# CCM_0008.net
KiCad netlist of a schematic drawn in EAGLE
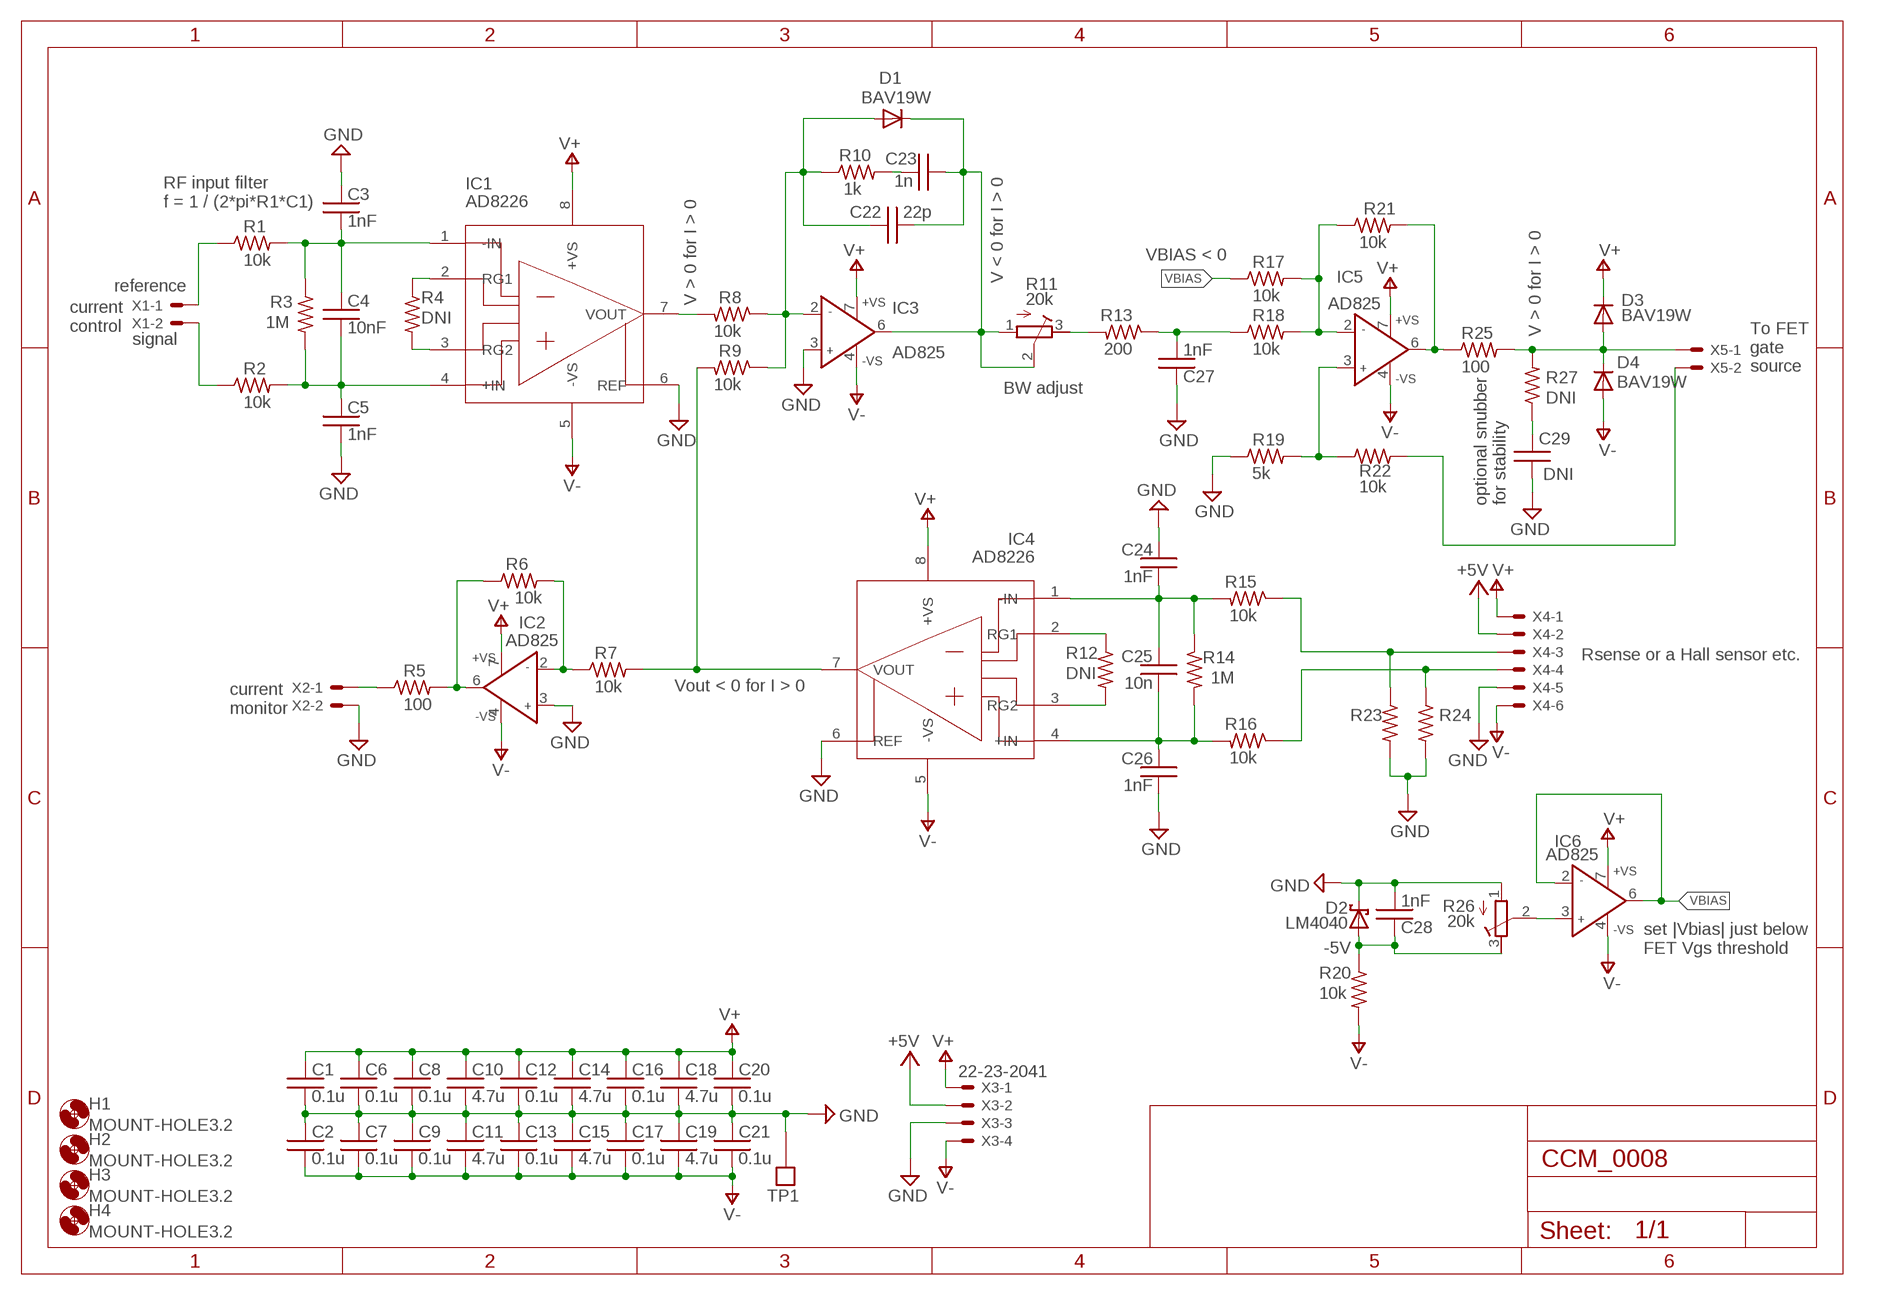
[diagram p0: schematic, sheet 1]

(export (version "E")
  (design (tool "Eeschema 10.0.6"))
  (components
    (comp (ref "C1")
      (value "0.1u")
      (footprint "eagle-import:0603")
      (libsource (lib "eagle-import") (part "C0603"))
    )
    (comp (ref "C2")
      (value "0.1u")
      (footprint "eagle-import:0603")
      (libsource (lib "eagle-import") (part "C0603"))
    )
    (comp (ref "C3")
      (value "1nF")
      (footprint "eagle-import:0603")
      (libsource (lib "eagle-import") (part "C0603"))
    )
    (comp (ref "C4")
      (value "10nF")
      (footprint "eagle-import:0603")
      (libsource (lib "eagle-import") (part "C0603"))
    )
    (comp (ref "C5")
      (value "1nF")
      (footprint "eagle-import:0603")
      (libsource (lib "eagle-import") (part "C0603"))
    )
    (comp (ref "C6")
      (value "0.1u")
      (footprint "eagle-import:0603")
      (libsource (lib "eagle-import") (part "C0603"))
    )
    (comp (ref "C7")
      (value "0.1u")
      (footprint "eagle-import:0603")
      (libsource (lib "eagle-import") (part "C0603"))
    )
    (comp (ref "C8")
      (value "0.1u")
      (footprint "eagle-import:0603")
      (libsource (lib "eagle-import") (part "C0603"))
    )
    (comp (ref "C9")
      (value "0.1u")
      (footprint "eagle-import:0603")
      (libsource (lib "eagle-import") (part "C0603"))
    )
    (comp (ref "C10")
      (value "4.7u")
      (footprint "eagle-import:0603")
      (libsource (lib "eagle-import") (part "C0603"))
    )
    (comp (ref "C11")
      (value "4.7u")
      (footprint "eagle-import:0603")
      (libsource (lib "eagle-import") (part "C0603"))
    )
    (comp (ref "C12")
      (value "0.1u")
      (footprint "eagle-import:0603")
      (libsource (lib "eagle-import") (part "C0603"))
    )
    (comp (ref "C13")
      (value "0.1u")
      (footprint "eagle-import:0603")
      (libsource (lib "eagle-import") (part "C0603"))
    )
    (comp (ref "C14")
      (value "4.7u")
      (footprint "eagle-import:0603")
      (libsource (lib "eagle-import") (part "C0603"))
    )
    (comp (ref "C15")
      (value "4.7u")
      (footprint "eagle-import:0603")
      (libsource (lib "eagle-import") (part "C0603"))
    )
    (comp (ref "C16")
      (value "0.1u")
      (footprint "eagle-import:0603")
      (libsource (lib "eagle-import") (part "C0603"))
    )
    (comp (ref "C17")
      (value "0.1u")
      (footprint "eagle-import:0603")
      (libsource (lib "eagle-import") (part "C0603"))
    )
    (comp (ref "C18")
      (value "4.7u")
      (footprint "eagle-import:0603")
      (libsource (lib "eagle-import") (part "C0603"))
    )
    (comp (ref "C19")
      (value "4.7u")
      (footprint "eagle-import:0603")
      (libsource (lib "eagle-import") (part "C0603"))
    )
    (comp (ref "C20")
      (value "0.1u")
      (footprint "eagle-import:0603")
      (libsource (lib "eagle-import") (part "C0603"))
    )
    (comp (ref "C21")
      (value "0.1u")
      (footprint "eagle-import:0603")
      (libsource (lib "eagle-import") (part "C0603"))
    )
    (comp (ref "C22")
      (value "22p")
      (footprint "eagle-import:0603")
      (libsource (lib "eagle-import") (part "C0603"))
    )
    (comp (ref "C23")
      (value "1n")
      (footprint "eagle-import:0603")
      (libsource (lib "eagle-import") (part "C0603"))
    )
    (comp (ref "C24")
      (value "1nF")
      (footprint "eagle-import:0603")
      (libsource (lib "eagle-import") (part "C0603"))
    )
    (comp (ref "C25")
      (value "10n")
      (footprint "eagle-import:0603")
      (libsource (lib "eagle-import") (part "C0603"))
    )
    (comp (ref "C26")
      (value "1nF")
      (footprint "eagle-import:0603")
      (libsource (lib "eagle-import") (part "C0603"))
    )
    (comp (ref "C27")
      (value "1nF")
      (footprint "eagle-import:0603")
      (libsource (lib "eagle-import") (part "C0603"))
    )
    (comp (ref "C28")
      (value "1nF")
      (footprint "eagle-import:0603")
      (libsource (lib "eagle-import") (part "C0603"))
    )
    (comp (ref "C29")
      (value "DNI")
      (footprint "eagle-import:0603")
      (libsource (lib "eagle-import") (part "C0603"))
    )
    (comp (ref "D1")
      (value "BAV19W")
      (footprint "eagle-import:SOD123")
      (libsource (lib "eagle-import") (part "DIODE-SOD123"))
    )
    (comp (ref "D2")
      (value "LM4040")
      (footprint "eagle-import:SOT23")
      (libsource (lib "eagle-import") (part "LM4040"))
    )
    (comp (ref "D3")
      (value "BAV19W")
      (footprint "eagle-import:SOD123")
      (libsource (lib "eagle-import") (part "DIODE-SOD123"))
    )
    (comp (ref "D4")
      (value "BAV19W")
      (footprint "eagle-import:SOD123")
      (libsource (lib "eagle-import") (part "DIODE-SOD123"))
    )
    (comp (ref "H1")
      (value "MOUNT-HOLE3.2")
      (footprint "eagle-import:3,2")
      (libsource (lib "eagle-import") (part "MOUNT-HOLE3.2"))
    )
    (comp (ref "H2")
      (value "MOUNT-HOLE3.2")
      (footprint "eagle-import:3,2")
      (libsource (lib "eagle-import") (part "MOUNT-HOLE3.2"))
    )
    (comp (ref "H3")
      (value "MOUNT-HOLE3.2")
      (footprint "eagle-import:3,2")
      (libsource (lib "eagle-import") (part "MOUNT-HOLE3.2"))
    )
    (comp (ref "H4")
      (value "MOUNT-HOLE3.2")
      (footprint "eagle-import:3,2")
      (libsource (lib "eagle-import") (part "MOUNT-HOLE3.2"))
    )
    (comp (ref "IC1")
      (value "AD8226")
      (footprint "eagle-import:SO08")
      (libsource (lib "eagle-import") (part "AD8226"))
    )
    (comp (ref "IC2")
      (value "AD825")
      (footprint "eagle-import:SO8")
      (fields (field (name "MF") "ALTERA CORPORATION") (field (name "MPN") "AD825ARZ"))
      (libsource (lib "eagle-import") (part "AD825_BR"))
    )
    (comp (ref "IC3")
      (value "AD825")
      (footprint "eagle-import:SO8")
      (fields (field (name "MF") "ALTERA CORPORATION") (field (name "MPN") "AD825ARZ"))
      (libsource (lib "eagle-import") (part "AD825_BR"))
    )
    (comp (ref "IC4")
      (value "AD8226")
      (footprint "eagle-import:SO08")
      (libsource (lib "eagle-import") (part "AD8226"))
    )
    (comp (ref "IC5")
      (value "AD825")
      (footprint "eagle-import:SO8")
      (fields (field (name "MF") "ALTERA CORPORATION") (field (name "MPN") "AD825ARZ"))
      (libsource (lib "eagle-import") (part "AD825_BR"))
    )
    (comp (ref "IC6")
      (value "AD825")
      (footprint "eagle-import:SO8")
      (fields (field (name "MF") "ALTERA CORPORATION") (field (name "MPN") "AD825ARZ"))
      (libsource (lib "eagle-import") (part "AD825_BR"))
    )
    (comp (ref "R1")
      (value "10k")
      (footprint "eagle-import:0603")
      (libsource (lib "eagle-import") (part "R0603"))
    )
    (comp (ref "R2")
      (value "10k")
      (footprint "eagle-import:0603")
      (libsource (lib "eagle-import") (part "R0603"))
    )
    (comp (ref "R3")
      (value "1M")
      (footprint "eagle-import:0603")
      (libsource (lib "eagle-import") (part "R0603"))
    )
    (comp (ref "R4")
      (value "DNI")
      (footprint "eagle-import:0603")
      (libsource (lib "eagle-import") (part "R0603"))
    )
    (comp (ref "R5")
      (value "100")
      (footprint "eagle-import:0603")
      (libsource (lib "eagle-import") (part "R0603"))
    )
    (comp (ref "R6")
      (value "10k")
      (footprint "eagle-import:0603")
      (libsource (lib "eagle-import") (part "R0603"))
    )
    (comp (ref "R7")
      (value "10k")
      (footprint "eagle-import:0603")
      (libsource (lib "eagle-import") (part "R0603"))
    )
    (comp (ref "R8")
      (value "10k")
      (footprint "eagle-import:0603")
      (libsource (lib "eagle-import") (part "R0603"))
    )
    (comp (ref "R9")
      (value "10k")
      (footprint "eagle-import:0603")
      (libsource (lib "eagle-import") (part "R0603"))
    )
    (comp (ref "R10")
      (value "1k")
      (footprint "eagle-import:0603")
      (libsource (lib "eagle-import") (part "R0603"))
    )
    (comp (ref "R11")
      (value "20k")
      (footprint "eagle-import:RTRIM3224W")
      (libsource (lib "eagle-import") (part "R-TRIMM3224W"))
    )
    (comp (ref "R12")
      (value "DNI")
      (footprint "eagle-import:0603")
      (libsource (lib "eagle-import") (part "R0603"))
    )
    (comp (ref "R13")
      (value "200")
      (footprint "eagle-import:0603")
      (libsource (lib "eagle-import") (part "R0603"))
    )
    (comp (ref "R14")
      (value "1M")
      (footprint "eagle-import:0603")
      (libsource (lib "eagle-import") (part "R0603"))
    )
    (comp (ref "R15")
      (value "10k")
      (footprint "eagle-import:0603")
      (libsource (lib "eagle-import") (part "R0603"))
    )
    (comp (ref "R16")
      (value "10k")
      (footprint "eagle-import:0603")
      (libsource (lib "eagle-import") (part "R0603"))
    )
    (comp (ref "R17")
      (value "10k")
      (footprint "eagle-import:0603")
      (libsource (lib "eagle-import") (part "R0603"))
    )
    (comp (ref "R18")
      (value "10k")
      (footprint "eagle-import:0603")
      (libsource (lib "eagle-import") (part "R0603"))
    )
    (comp (ref "R19")
      (value "5k")
      (footprint "eagle-import:0603")
      (libsource (lib "eagle-import") (part "R0603"))
    )
    (comp (ref "R20")
      (value "10k")
      (footprint "eagle-import:0603")
      (libsource (lib "eagle-import") (part "R0603"))
    )
    (comp (ref "R21")
      (value "10k")
      (footprint "eagle-import:0603")
      (libsource (lib "eagle-import") (part "R0603"))
    )
    (comp (ref "R22")
      (value "10k")
      (footprint "eagle-import:0603")
      (libsource (lib "eagle-import") (part "R0603"))
    )
    (comp (ref "R23")
      (value "***")
      (footprint "eagle-import:0603")
      (libsource (lib "eagle-import") (part "R0603"))
    )
    (comp (ref "R24")
      (value "***")
      (footprint "eagle-import:0603")
      (libsource (lib "eagle-import") (part "R0603"))
    )
    (comp (ref "R25")
      (value "100")
      (footprint "eagle-import:0603")
      (libsource (lib "eagle-import") (part "R0603"))
    )
    (comp (ref "R26")
      (value "20k")
      (footprint "eagle-import:RTRIM3224W")
      (libsource (lib "eagle-import") (part "R-TRIMM3224W"))
    )
    (comp (ref "R27")
      (value "DNI")
      (footprint "eagle-import:0603")
      (libsource (lib "eagle-import") (part "R0603"))
    )
    (comp (ref "TP1")
      (value "TESTPOINT")
      (footprint "eagle-import:TESTPOINT")
      (libsource (lib "eagle-import") (part "TESTPOINT"))
    )
    (comp (ref "X1")
      (value "22-23-2021")
      (footprint "eagle-import:22-23-2021")
      (fields (field (name "MF") "MOLEX"))
      (libsource (lib "eagle-import") (part "22-23-2021"))
    )
    (comp (ref "X2")
      (value "22-23-2021")
      (footprint "eagle-import:22-23-2021")
      (fields (field (name "MF") "MOLEX"))
      (libsource (lib "eagle-import") (part "22-23-2021"))
    )
    (comp (ref "X3")
      (value "22-23-2041")
      (footprint "eagle-import:22-23-2041")
      (fields (field (name "MF") "MOLEX"))
      (libsource (lib "eagle-import") (part "22-23-2041"))
    )
    (comp (ref "X4")
      (value "22-23-2061")
      (footprint "eagle-import:22-23-2061")
      (fields (field (name "MF") "MOLEX"))
      (libsource (lib "eagle-import") (part "22-23-2061"))
    )
    (comp (ref "X5")
      (value "22-23-2021")
      (footprint "eagle-import:22-23-2021")
      (fields (field (name "MF") "MOLEX"))
      (libsource (lib "eagle-import") (part "22-23-2021"))
    )
  )
  (nets
    (net (code "1") (name "+5V") (class "Default")
      (node (ref "X3") (pin "2") (pinfunction "S_2") (pintype "passive"))
      (node (ref "X4") (pin "2") (pinfunction "S_2") (pintype "passive"))
    )
    (net (code "2") (name "GND") (class "Default")
      (node (ref "C1") (pin "2") (pinfunction "2_2") (pintype "passive"))
      (node (ref "C10") (pin "2") (pinfunction "2_2") (pintype "passive"))
      (node (ref "C11") (pin "1") (pinfunction "1_1") (pintype "passive"))
      (node (ref "C12") (pin "2") (pinfunction "2_2") (pintype "passive"))
      (node (ref "C13") (pin "1") (pinfunction "1_1") (pintype "passive"))
      (node (ref "C14") (pin "2") (pinfunction "2_2") (pintype "passive"))
      (node (ref "C15") (pin "1") (pinfunction "1_1") (pintype "passive"))
      (node (ref "C16") (pin "2") (pinfunction "2_2") (pintype "passive"))
      (node (ref "C17") (pin "1") (pinfunction "1_1") (pintype "passive"))
      (node (ref "C18") (pin "2") (pinfunction "2_2") (pintype "passive"))
      (node (ref "C19") (pin "1") (pinfunction "1_1") (pintype "passive"))
      (node (ref "C2") (pin "1") (pinfunction "1_1") (pintype "passive"))
      (node (ref "C20") (pin "2") (pinfunction "2_2") (pintype "passive"))
      (node (ref "C21") (pin "1") (pinfunction "1_1") (pintype "passive"))
      (node (ref "C24") (pin "1") (pinfunction "1_1") (pintype "passive"))
      (node (ref "C26") (pin "2") (pinfunction "2_2") (pintype "passive"))
      (node (ref "C27") (pin "1") (pinfunction "1_1") (pintype "passive"))
      (node (ref "C28") (pin "2") (pinfunction "2_2") (pintype "passive"))
      (node (ref "C29") (pin "2") (pinfunction "2_2") (pintype "passive"))
      (node (ref "C3") (pin "1") (pinfunction "1_1") (pintype "passive"))
      (node (ref "C5") (pin "2") (pinfunction "2_2") (pintype "passive"))
      (node (ref "C6") (pin "2") (pinfunction "2_2") (pintype "passive"))
      (node (ref "C7") (pin "1") (pinfunction "1_1") (pintype "passive"))
      (node (ref "C8") (pin "2") (pinfunction "2_2") (pintype "passive"))
      (node (ref "C9") (pin "1") (pinfunction "1_1") (pintype "passive"))
      (node (ref "D2") (pin "1") (pinfunction "C_1") (pintype "passive"))
      (node (ref "IC1") (pin "6") (pinfunction "REF_6") (pintype "bidirectional"))
      (node (ref "IC2") (pin "3") (pinfunction "IN+_3") (pintype "input"))
      (node (ref "IC3") (pin "3") (pinfunction "IN+_3") (pintype "input"))
      (node (ref "IC4") (pin "6") (pinfunction "REF_6") (pintype "bidirectional"))
      (node (ref "R19") (pin "1") (pinfunction "1_1") (pintype "passive"))
      (node (ref "R23") (pin "2") (pinfunction "2_2") (pintype "passive"))
      (node (ref "R24") (pin "2") (pinfunction "2_2") (pintype "passive"))
      (node (ref "R26") (pin "1") (pinfunction "A_1") (pintype "passive"))
      (node (ref "TP1") (pin "P$1") (pinfunction "P$1_P$1") (pintype "bidirectional"))
      (node (ref "X2") (pin "2") (pinfunction "S_2") (pintype "passive"))
      (node (ref "X3") (pin "3") (pinfunction "S_3") (pintype "passive"))
      (node (ref "X4") (pin "5") (pinfunction "S_5") (pintype "passive"))
    )
    (net (code "3") (name "Net-(C23-Pad2)") (class "Default")
      (node (ref "C23") (pin "2") (pinfunction "2_2") (pintype "passive"))
      (node (ref "R10") (pin "2") (pinfunction "2_2") (pintype "passive"))
    )
    (net (code "4") (name "Net-(C27-Pad2)") (class "Default")
      (node (ref "C27") (pin "2") (pinfunction "2_2") (pintype "passive"))
      (node (ref "R13") (pin "1") (pinfunction "1_1") (pintype "passive"))
      (node (ref "R18") (pin "1") (pinfunction "1_1") (pintype "passive"))
    )
    (net (code "5") (name "Net-(C29-Pad1)") (class "Default")
      (node (ref "C29") (pin "1") (pinfunction "1_1") (pintype "passive"))
      (node (ref "R27") (pin "1") (pinfunction "1_1") (pintype "passive"))
    )
    (net (code "6") (name "Net-(D2-A)") (class "Default")
      (node (ref "C28") (pin "1") (pinfunction "1_1") (pintype "passive"))
      (node (ref "D2") (pin "2") (pinfunction "A_2") (pintype "passive"))
      (node (ref "R20") (pin "1") (pinfunction "1_1") (pintype "passive"))
      (node (ref "R26") (pin "3") (pinfunction "E_3") (pintype "passive"))
    )
    (net (code "7") (name "Net-(IC1-+IN)") (class "Default")
      (node (ref "C4") (pin "2") (pinfunction "2_2") (pintype "passive"))
      (node (ref "C5") (pin "1") (pinfunction "1_1") (pintype "passive"))
      (node (ref "IC1") (pin "4") (pinfunction "+IN_4") (pintype "bidirectional"))
      (node (ref "R2") (pin "2") (pinfunction "2_2") (pintype "passive"))
      (node (ref "R3") (pin "2") (pinfunction "2_2") (pintype "passive"))
    )
    (net (code "8") (name "Net-(IC1--IN)") (class "Default")
      (node (ref "C3") (pin "2") (pinfunction "2_2") (pintype "passive"))
      (node (ref "C4") (pin "1") (pinfunction "1_1") (pintype "passive"))
      (node (ref "IC1") (pin "1") (pinfunction "-IN_1") (pintype "bidirectional"))
      (node (ref "R1") (pin "2") (pinfunction "2_2") (pintype "passive"))
      (node (ref "R3") (pin "1") (pinfunction "1_1") (pintype "passive"))
    )
    (net (code "9") (name "Net-(IC1-RG1)") (class "Default")
      (node (ref "IC1") (pin "2") (pinfunction "RG1_2") (pintype "bidirectional"))
      (node (ref "R4") (pin "1") (pinfunction "1_1") (pintype "passive"))
    )
    (net (code "10") (name "Net-(IC1-RG2)") (class "Default")
      (node (ref "IC1") (pin "3") (pinfunction "RG2_3") (pintype "bidirectional"))
      (node (ref "R4") (pin "2") (pinfunction "2_2") (pintype "passive"))
    )
    (net (code "11") (name "Net-(IC1-VOUT)") (class "Default")
      (node (ref "IC1") (pin "7") (pinfunction "VOUT_7") (pintype "bidirectional"))
      (node (ref "R8") (pin "2") (pinfunction "2_2") (pintype "passive"))
    )
    (net (code "12") (name "Net-(IC2-IN-)") (class "Default")
      (node (ref "IC2") (pin "2") (pinfunction "IN-_2") (pintype "input"))
      (node (ref "R6") (pin "2") (pinfunction "2_2") (pintype "passive"))
      (node (ref "R7") (pin "1") (pinfunction "1_1") (pintype "passive"))
    )
    (net (code "13") (name "Net-(IC2-OUT)") (class "Default")
      (node (ref "IC2") (pin "6") (pinfunction "OUT_6") (pintype "output"))
      (node (ref "R5") (pin "2") (pinfunction "2_2") (pintype "passive"))
      (node (ref "R6") (pin "1") (pinfunction "1_1") (pintype "passive"))
    )
    (net (code "14") (name "Net-(IC3-IN-)") (class "Default")
      (node (ref "C22") (pin "2") (pinfunction "2_2") (pintype "passive"))
      (node (ref "D1") (pin "A") (pinfunction "A_A") (pintype "passive"))
      (node (ref "IC3") (pin "2") (pinfunction "IN-_2") (pintype "input"))
      (node (ref "R10") (pin "1") (pinfunction "1_1") (pintype "passive"))
      (node (ref "R8") (pin "1") (pinfunction "1_1") (pintype "passive"))
      (node (ref "R9") (pin "1") (pinfunction "1_1") (pintype "passive"))
    )
    (net (code "15") (name "Net-(IC3-OUT)") (class "Default")
      (node (ref "C22") (pin "1") (pinfunction "1_1") (pintype "passive"))
      (node (ref "C23") (pin "1") (pinfunction "1_1") (pintype "passive"))
      (node (ref "D1") (pin "C") (pinfunction "C_C") (pintype "passive"))
      (node (ref "IC3") (pin "6") (pinfunction "OUT_6") (pintype "output"))
      (node (ref "R11") (pin "1") (pinfunction "A_1") (pintype "passive"))
      (node (ref "R11") (pin "2") (pinfunction "S_2") (pintype "passive"))
    )
    (net (code "16") (name "Net-(IC4-+IN)") (class "Default")
      (node (ref "C25") (pin "2") (pinfunction "2_2") (pintype "passive"))
      (node (ref "C26") (pin "1") (pinfunction "1_1") (pintype "passive"))
      (node (ref "IC4") (pin "4") (pinfunction "+IN_4") (pintype "bidirectional"))
      (node (ref "R14") (pin "2") (pinfunction "2_2") (pintype "passive"))
      (node (ref "R16") (pin "2") (pinfunction "2_2") (pintype "passive"))
    )
    (net (code "17") (name "Net-(IC4--IN)") (class "Default")
      (node (ref "C24") (pin "2") (pinfunction "2_2") (pintype "passive"))
      (node (ref "C25") (pin "1") (pinfunction "1_1") (pintype "passive"))
      (node (ref "IC4") (pin "1") (pinfunction "-IN_1") (pintype "bidirectional"))
      (node (ref "R14") (pin "1") (pinfunction "1_1") (pintype "passive"))
      (node (ref "R15") (pin "2") (pinfunction "2_2") (pintype "passive"))
    )
    (net (code "18") (name "Net-(IC4-RG1)") (class "Default")
      (node (ref "IC4") (pin "2") (pinfunction "RG1_2") (pintype "bidirectional"))
      (node (ref "R12") (pin "1") (pinfunction "1_1") (pintype "passive"))
    )
    (net (code "19") (name "Net-(IC4-RG2)") (class "Default")
      (node (ref "IC4") (pin "3") (pinfunction "RG2_3") (pintype "bidirectional"))
      (node (ref "R12") (pin "2") (pinfunction "2_2") (pintype "passive"))
    )
    (net (code "20") (name "Net-(IC4-VOUT)") (class "Default")
      (node (ref "IC4") (pin "7") (pinfunction "VOUT_7") (pintype "bidirectional"))
      (node (ref "R7") (pin "2") (pinfunction "2_2") (pintype "passive"))
      (node (ref "R9") (pin "2") (pinfunction "2_2") (pintype "passive"))
    )
    (net (code "21") (name "Net-(IC5-IN+)") (class "Default")
      (node (ref "IC5") (pin "3") (pinfunction "IN+_3") (pintype "input"))
      (node (ref "R19") (pin "2") (pinfunction "2_2") (pintype "passive"))
      (node (ref "R22") (pin "1") (pinfunction "1_1") (pintype "passive"))
    )
    (net (code "22") (name "Net-(IC5-IN-)") (class "Default")
      (node (ref "IC5") (pin "2") (pinfunction "IN-_2") (pintype "input"))
      (node (ref "R17") (pin "2") (pinfunction "2_2") (pintype "passive"))
      (node (ref "R18") (pin "2") (pinfunction "2_2") (pintype "passive"))
      (node (ref "R21") (pin "1") (pinfunction "1_1") (pintype "passive"))
    )
    (net (code "23") (name "Net-(IC5-OUT)") (class "Default")
      (node (ref "IC5") (pin "6") (pinfunction "OUT_6") (pintype "output"))
      (node (ref "R21") (pin "2") (pinfunction "2_2") (pintype "passive"))
      (node (ref "R25") (pin "1") (pinfunction "1_1") (pintype "passive"))
    )
    (net (code "24") (name "Net-(IC6-IN+)") (class "Default")
      (node (ref "IC6") (pin "3") (pinfunction "IN+_3") (pintype "input"))
      (node (ref "R26") (pin "2") (pinfunction "S_2") (pintype "passive"))
    )
    (net (code "25") (name "Net-(R11-E)") (class "Default")
      (node (ref "R11") (pin "3") (pinfunction "E_3") (pintype "passive"))
      (node (ref "R13") (pin "2") (pinfunction "2_2") (pintype "passive"))
    )
    (net (code "26") (name "Net-(X1A-S)") (class "Default")
      (node (ref "R1") (pin "1") (pinfunction "1_1") (pintype "passive"))
      (node (ref "X1") (pin "1") (pinfunction "S_1") (pintype "passive"))
    )
    (net (code "27") (name "Net-(X1B-S)") (class "Default")
      (node (ref "R2") (pin "1") (pinfunction "1_1") (pintype "passive"))
      (node (ref "X1") (pin "2") (pinfunction "S_2") (pintype "passive"))
    )
    (net (code "28") (name "Net-(X2A-S)") (class "Default")
      (node (ref "R5") (pin "1") (pinfunction "1_1") (pintype "passive"))
      (node (ref "X2") (pin "1") (pinfunction "S_1") (pintype "passive"))
    )
    (net (code "29") (name "Net-(X4C-S)") (class "Default")
      (node (ref "R15") (pin "1") (pinfunction "1_1") (pintype "passive"))
      (node (ref "R23") (pin "1") (pinfunction "1_1") (pintype "passive"))
      (node (ref "X4") (pin "3") (pinfunction "S_3") (pintype "passive"))
    )
    (net (code "30") (name "Net-(X4D-S)") (class "Default")
      (node (ref "R16") (pin "1") (pinfunction "1_1") (pintype "passive"))
      (node (ref "R24") (pin "1") (pinfunction "1_1") (pintype "passive"))
      (node (ref "X4") (pin "4") (pinfunction "S_4") (pintype "passive"))
    )
    (net (code "31") (name "Net-(X5A-S)") (class "Default")
      (node (ref "D3") (pin "A") (pinfunction "A_A") (pintype "passive"))
      (node (ref "D4") (pin "C") (pinfunction "C_C") (pintype "passive"))
      (node (ref "R25") (pin "2") (pinfunction "2_2") (pintype "passive"))
      (node (ref "R27") (pin "2") (pinfunction "2_2") (pintype "passive"))
      (node (ref "X5") (pin "1") (pinfunction "S_1") (pintype "passive"))
    )
    (net (code "32") (name "Net-(X5B-S)") (class "Default")
      (node (ref "R22") (pin "2") (pinfunction "2_2") (pintype "passive"))
      (node (ref "X5") (pin "2") (pinfunction "S_2") (pintype "passive"))
    )
    (net (code "33") (name "V+") (class "Default")
      (node (ref "C1") (pin "1") (pinfunction "1_1") (pintype "passive"))
      (node (ref "C10") (pin "1") (pinfunction "1_1") (pintype "passive"))
      (node (ref "C12") (pin "1") (pinfunction "1_1") (pintype "passive"))
      (node (ref "C14") (pin "1") (pinfunction "1_1") (pintype "passive"))
      (node (ref "C16") (pin "1") (pinfunction "1_1") (pintype "passive"))
      (node (ref "C18") (pin "1") (pinfunction "1_1") (pintype "passive"))
      (node (ref "C20") (pin "1") (pinfunction "1_1") (pintype "passive"))
      (node (ref "C6") (pin "1") (pinfunction "1_1") (pintype "passive"))
      (node (ref "C8") (pin "1") (pinfunction "1_1") (pintype "passive"))
      (node (ref "D3") (pin "C") (pinfunction "C_C") (pintype "passive"))
      (node (ref "IC1") (pin "8") (pinfunction "+VS_8") (pintype "bidirectional"))
      (node (ref "IC2") (pin "7") (pinfunction "+VS_7") (pintype "input"))
      (node (ref "IC3") (pin "7") (pinfunction "+VS_7") (pintype "input"))
      (node (ref "IC4") (pin "8") (pinfunction "+VS_8") (pintype "bidirectional"))
      (node (ref "IC5") (pin "7") (pinfunction "+VS_7") (pintype "input"))
      (node (ref "IC6") (pin "7") (pinfunction "+VS_7") (pintype "input"))
      (node (ref "X3") (pin "1") (pinfunction "S_1") (pintype "passive"))
      (node (ref "X4") (pin "1") (pinfunction "S_1") (pintype "passive"))
    )
    (net (code "34") (name "V-") (class "Default")
      (node (ref "C11") (pin "2") (pinfunction "2_2") (pintype "passive"))
      (node (ref "C13") (pin "2") (pinfunction "2_2") (pintype "passive"))
      (node (ref "C15") (pin "2") (pinfunction "2_2") (pintype "passive"))
      (node (ref "C17") (pin "2") (pinfunction "2_2") (pintype "passive"))
      (node (ref "C19") (pin "2") (pinfunction "2_2") (pintype "passive"))
      (node (ref "C2") (pin "2") (pinfunction "2_2") (pintype "passive"))
      (node (ref "C21") (pin "2") (pinfunction "2_2") (pintype "passive"))
      (node (ref "C7") (pin "2") (pinfunction "2_2") (pintype "passive"))
      (node (ref "C9") (pin "2") (pinfunction "2_2") (pintype "passive"))
      (node (ref "D4") (pin "A") (pinfunction "A_A") (pintype "passive"))
      (node (ref "IC1") (pin "5") (pinfunction "-VS_5") (pintype "bidirectional"))
      (node (ref "IC2") (pin "4") (pinfunction "-VS_4") (pintype "input"))
      (node (ref "IC3") (pin "4") (pinfunction "-VS_4") (pintype "input"))
      (node (ref "IC4") (pin "5") (pinfunction "-VS_5") (pintype "bidirectional"))
      (node (ref "IC5") (pin "4") (pinfunction "-VS_4") (pintype "input"))
      (node (ref "IC6") (pin "4") (pinfunction "-VS_4") (pintype "input"))
      (node (ref "R20") (pin "2") (pinfunction "2_2") (pintype "passive"))
      (node (ref "X3") (pin "4") (pinfunction "S_4") (pintype "passive"))
      (node (ref "X4") (pin "6") (pinfunction "S_6") (pintype "passive"))
    )
    (net (code "35") (name "VBIAS") (class "Default")
      (node (ref "IC6") (pin "2") (pinfunction "IN-_2") (pintype "input"))
      (node (ref "IC6") (pin "6") (pinfunction "OUT_6") (pintype "output"))
      (node (ref "R17") (pin "1") (pinfunction "1_1") (pintype "passive"))
    )
  )
)
